# Breakout_DL_IP-M4_rev02.net
KiCad netlist of a schematic drawn in EAGLE
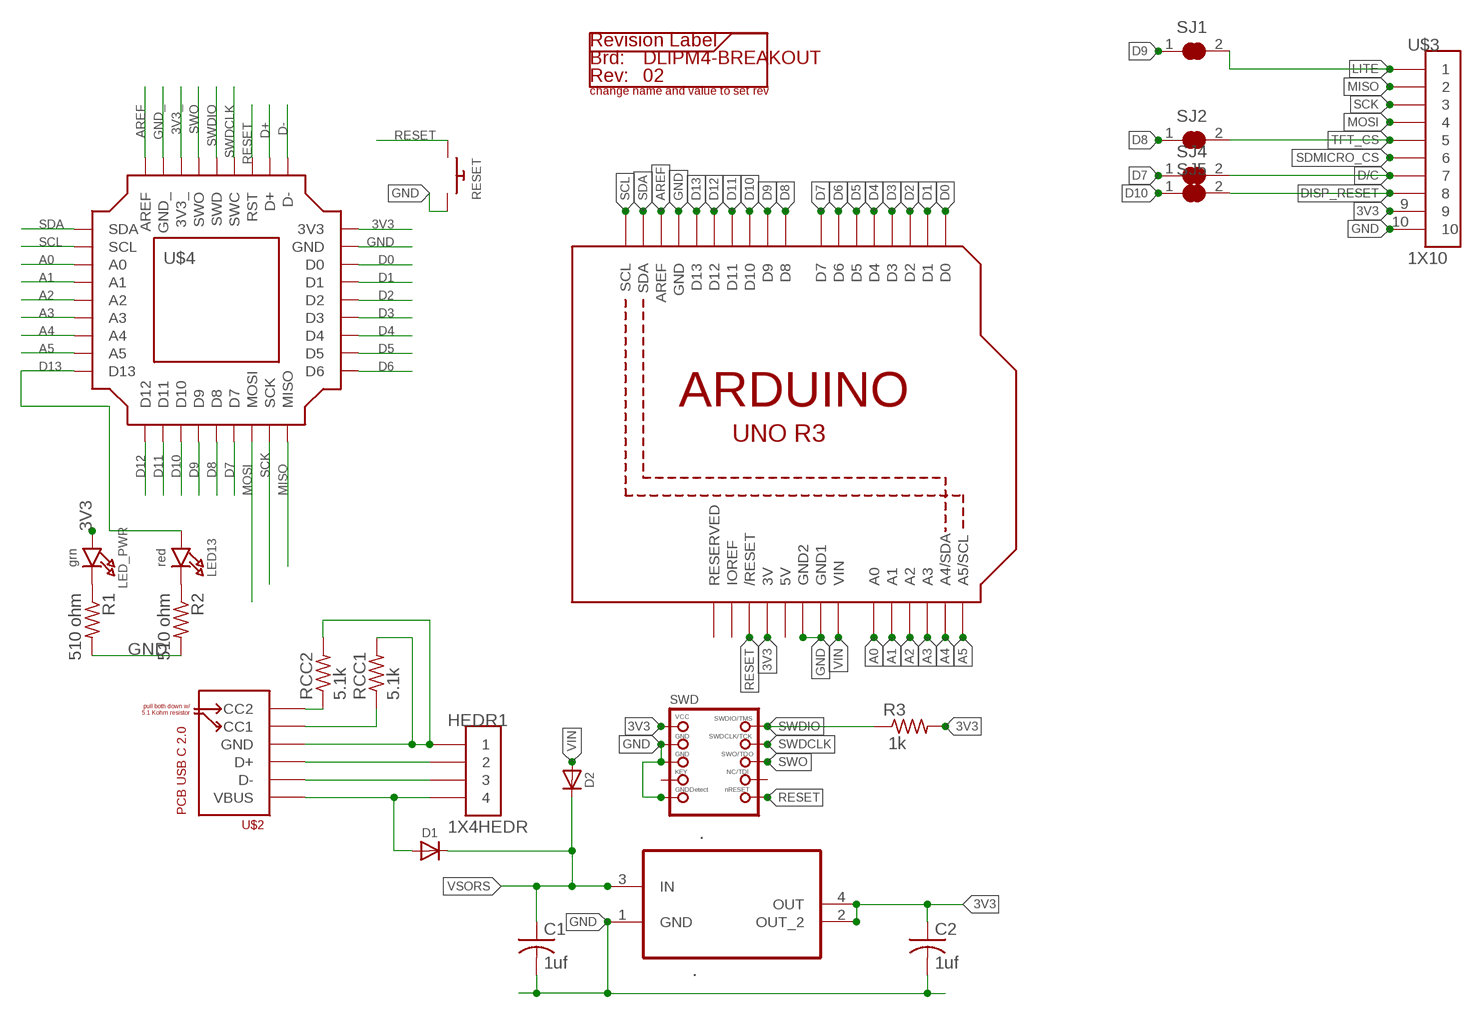
[diagram p0: schematic, sheet 1]

(export (version "E")
  (design (tool "Eeschema 10.0.6"))
  (components
    (comp (ref ".")
      (value ".")
      (footprint "eagle-import:SOT230P700X180-4N")
      (fields (field (name "MF") "Analog Devices") (field (name "MP") "ADP3339AKCZ-3.3-RL"))
      (libsource (lib "eagle-import") (part "VREG-1.5A-3.3V-LRG"))
    )
    (comp (ref "C1")
      (value "1uf")
      (footprint "eagle-import:TG-0603")
      (libsource (lib "eagle-import") (part "C-TG_0603"))
    )
    (comp (ref "C2")
      (value "1uf")
      (footprint "eagle-import:TG-0603")
      (libsource (lib "eagle-import") (part "C-TG_0603"))
    )
    (comp (ref "D1")
      (value "DIODESOD-123")
      (footprint "eagle-import:SOD-123")
      (libsource (lib "eagle-import") (part "DIODESOD-123"))
    )
    (comp (ref "D2")
      (value "DIODESOD-123")
      (footprint "eagle-import:SOD-123")
      (libsource (lib "eagle-import") (part "DIODESOD-123"))
    )
    (comp (ref "DLIPM4-BREAKOUT")
      (value "02")
      (footprint "eagle-import:REVISION_LABEL_LONG")
      (libsource (lib "eagle-import") (part "REVISION_LABELLONG"))
    )
    (comp (ref "HEDR1")
      (value "1X4HEDR")
      (footprint "eagle-import:1X4_HEDR")
      (libsource (lib "eagle-import") (part "1X4HEDR"))
    )
    (comp (ref "LED13")
      (value "red")
      (footprint "eagle-import:MICROBUILDER_CHIPLED_1206_NOOUTLINE")
      (libsource (lib "eagle-import") (part "LED-MICROBUILDER1206_NOOUTLINE"))
    )
    (comp (ref "LED_PWR")
      (value "grn")
      (footprint "eagle-import:MICROBUILDER_CHIPLED_1206_NOOUTLINE")
      (libsource (lib "eagle-import") (part "LED-MICROBUILDER1206_NOOUTLINE"))
    )
    (comp (ref "R1")
      (value "510 ohm")
      (footprint "eagle-import:TG-0603")
      (libsource (lib "eagle-import") (part "R_TG_0603"))
    )
    (comp (ref "R2")
      (value "510 ohm")
      (footprint "eagle-import:TG-0603")
      (libsource (lib "eagle-import") (part "R_TG_0603"))
    )
    (comp (ref "R3")
      (value "1k")
      (footprint "eagle-import:TG-0603")
      (libsource (lib "eagle-import") (part "R_TG_0603"))
    )
    (comp (ref "RCC1")
      (value "5.1k")
      (footprint "eagle-import:TG-0603")
      (libsource (lib "eagle-import") (part "R_TG_0603"))
    )
    (comp (ref "RCC2")
      (value "5.1k")
      (footprint "eagle-import:TG-0603")
      (libsource (lib "eagle-import") (part "R_TG_0603"))
    )
    (comp (ref "RESET")
      (value "SWITCH_PUSHBUTTONEVQ-PE")
      (footprint "eagle-import:TACT_PANA-EVQ")
      (libsource (lib "eagle-import") (part "SWITCH_PUSHBUTTONEVQ-PE"))
    )
    (comp (ref "SJ1")
      (value "JUMPER_CLOSEDTEMP")
      (footprint "eagle-import:SOLDERJUMPER_CLOSEDWIRE")
      (libsource (lib "eagle-import") (part "JUMPER_CLOSEDTEMP"))
    )
    (comp (ref "SJ2")
      (value "JUMPER_CLOSEDTEMP")
      (footprint "eagle-import:SOLDERJUMPER_CLOSEDWIRE")
      (libsource (lib "eagle-import") (part "JUMPER_CLOSEDTEMP"))
    )
    (comp (ref "SJ4")
      (value "JUMPER_CLOSEDTEMP")
      (footprint "eagle-import:SOLDERJUMPER_CLOSEDWIRE")
      (libsource (lib "eagle-import") (part "JUMPER_CLOSEDTEMP"))
    )
    (comp (ref "SJ5")
      (value "JUMPER_CLOSEDTEMP")
      (footprint "eagle-import:SOLDERJUMPER_CLOSEDWIRE")
      (libsource (lib "eagle-import") (part "JUMPER_CLOSEDTEMP"))
    )
    (comp (ref "SWD")
      (value "CON-SWD-JTAG-CORTEXBOXPOSTS")
      (footprint "eagle-import:2X05_1.27MM_BOX_POSTS")
      (libsource (lib "eagle-import") (part "CON-SWD-JTAG-CORTEXBOXPOSTS"))
    )
    (comp (ref "U$2")
      (value "USB-C-PCB-USB-2.0-TYPE-CDS_2")
      (footprint "eagle-import:USB_TYPE_C_DS_2")
      (libsource (lib "eagle-import") (part "USB-C-PCB-USB-2.0-TYPE-CDS_2"))
    )
    (comp (ref "U$3")
      (value "1X10")
      (footprint "eagle-import:1X10_HEDR")
      (libsource (lib "eagle-import") (part "1X10"))
    )
    (comp (ref "U$4")
      (value "DATALORE_IP_M4FOOTPRINT")
      (footprint "eagle-import:DL_IP_36-100MIL-FOOTPRINT")
      (libsource (lib "eagle-import") (part "DATALORE_IP_M4FOOTPRINT"))
    )
    (comp (ref "U1")
      (value "ARDUINOR3-BPLACE")
      (footprint "eagle-import:ARDUINOR3-BPLACE")
      (libsource (lib "eagle-import") (part "ARDUINOR3-BPLACE"))
    )
  )
  (nets
    (net (code "1") (name "/3V3_") (class "Default")
      (node (ref "U$4") (pin "3") (pinfunction "3V3__3") (pintype "bidirectional"))
    )
    (net (code "2") (name "/5V") (class "Default")
      (node (ref "U1") (pin "5V") (pinfunction "5V_5V") (pintype "power_in"))
    )
    (net (code "3") (name "/D+") (class "Default")
      (node (ref "HEDR1") (pin "2") (pinfunction "2_2") (pintype "bidirectional"))
      (node (ref "U$2") (pin "A6") (pinfunction "D+_A6") (pintype "bidirectional"))
      (node (ref "U$2") (pin "B6") (pinfunction "D+_B6") (pintype "bidirectional"))
      (node (ref "U$4") (pin "8") (pinfunction "D+_8") (pintype "bidirectional"))
    )
    (net (code "4") (name "/D-") (class "Default")
      (node (ref "HEDR1") (pin "3") (pinfunction "3_3") (pintype "bidirectional"))
      (node (ref "U$2") (pin "A7") (pinfunction "D-_A7") (pintype "bidirectional"))
      (node (ref "U$2") (pin "B7") (pinfunction "D-_B7") (pintype "bidirectional"))
      (node (ref "U$4") (pin "9") (pinfunction "D-_9") (pintype "bidirectional"))
    )
    (net (code "5") (name "/GND_") (class "Default")
      (node (ref "U$4") (pin "2") (pinfunction "GND__2") (pintype "bidirectional"))
    )
    (net (code "6") (name "3V3") (class "Default")
      (node (ref ".") (pin "2") (pinfunction "OUT_2_2") (pintype "output"))
      (node (ref ".") (pin "4") (pinfunction "OUT_4") (pintype "output"))
      (node (ref "C2") (pin "1") (pinfunction "1_1") (pintype "passive"))
      (node (ref "LED_PWR") (pin "A") (pinfunction "A_A") (pintype "passive"))
      (node (ref "R3") (pin "2") (pinfunction "2_2") (pintype "passive"))
      (node (ref "SWD") (pin "1") (pinfunction "VCC_1") (pintype "power_in"))
      (node (ref "U$3") (pin "9") (pinfunction "9_9") (pintype "bidirectional"))
      (node (ref "U$4") (pin "10") (pinfunction "3V3_10") (pintype "bidirectional"))
      (node (ref "U1") (pin "3V") (pinfunction "3V_3V") (pintype "power_in"))
    )
    (net (code "7") (name "A0") (class "Default")
      (node (ref "U$4") (pin "34") (pinfunction "A0_34") (pintype "bidirectional"))
      (node (ref "U1") (pin "A0") (pinfunction "A0_A0") (pintype "bidirectional"))
    )
    (net (code "8") (name "A1") (class "Default")
      (node (ref "U$4") (pin "33") (pinfunction "A1_33") (pintype "bidirectional"))
      (node (ref "U1") (pin "A1") (pinfunction "A1_A1") (pintype "bidirectional"))
    )
    (net (code "9") (name "A2") (class "Default")
      (node (ref "U$4") (pin "32") (pinfunction "A2_32") (pintype "bidirectional"))
      (node (ref "U1") (pin "A2") (pinfunction "A2_A2") (pintype "bidirectional"))
    )
    (net (code "10") (name "A3") (class "Default")
      (node (ref "U$4") (pin "31") (pinfunction "A3_31") (pintype "bidirectional"))
      (node (ref "U1") (pin "A3") (pinfunction "A3_A3") (pintype "bidirectional"))
    )
    (net (code "11") (name "A4") (class "Default")
      (node (ref "U$4") (pin "30") (pinfunction "A4_30") (pintype "bidirectional"))
      (node (ref "U1") (pin "A4") (pinfunction "A4/SDA_A4") (pintype "bidirectional"))
    )
    (net (code "12") (name "A5") (class "Default")
      (node (ref "U$4") (pin "29") (pinfunction "A5_29") (pintype "bidirectional"))
      (node (ref "U1") (pin "A5") (pinfunction "A5/SCL_A5") (pintype "bidirectional"))
    )
    (net (code "13") (name "AREF") (class "Default")
      (node (ref "U$4") (pin "1") (pinfunction "AREF_1") (pintype "bidirectional"))
      (node (ref "U1") (pin "AREF") (pinfunction "AREF_AREF") (pintype "bidirectional"))
    )
    (net (code "14") (name "D0") (class "Default")
      (node (ref "U$4") (pin "12") (pinfunction "D0_12") (pintype "bidirectional"))
      (node (ref "U1") (pin "D0") (pinfunction "D0_D0") (pintype "bidirectional"))
    )
    (net (code "15") (name "D1") (class "Default")
      (node (ref "U$4") (pin "13") (pinfunction "D1_13") (pintype "bidirectional"))
      (node (ref "U1") (pin "D1") (pinfunction "D1_D1") (pintype "bidirectional"))
    )
    (net (code "16") (name "D2") (class "Default")
      (node (ref "U$4") (pin "14") (pinfunction "D2_14") (pintype "bidirectional"))
      (node (ref "U1") (pin "D2") (pinfunction "D2_D2") (pintype "bidirectional"))
    )
    (net (code "17") (name "D3") (class "Default")
      (node (ref "U$4") (pin "15") (pinfunction "D3_15") (pintype "bidirectional"))
      (node (ref "U1") (pin "D3") (pinfunction "D3_D3") (pintype "bidirectional"))
    )
    (net (code "18") (name "D4") (class "Default")
      (node (ref "U$4") (pin "16") (pinfunction "D4_16") (pintype "bidirectional"))
      (node (ref "U1") (pin "D4") (pinfunction "D4_D4") (pintype "bidirectional"))
    )
    (net (code "19") (name "D5") (class "Default")
      (node (ref "U$4") (pin "17") (pinfunction "D5_17") (pintype "bidirectional"))
      (node (ref "U1") (pin "D5") (pinfunction "D5_D5") (pintype "bidirectional"))
    )
    (net (code "20") (name "D6") (class "Default")
      (node (ref "U$4") (pin "18") (pinfunction "D6_18") (pintype "bidirectional"))
      (node (ref "U1") (pin "D6") (pinfunction "D6_D6") (pintype "bidirectional"))
    )
    (net (code "21") (name "D7") (class "Default")
      (node (ref "SJ4") (pin "1") (pinfunction "1_1") (pintype "passive"))
      (node (ref "U$4") (pin "22") (pinfunction "D7_22") (pintype "bidirectional"))
      (node (ref "U1") (pin "D7") (pinfunction "D7_D7") (pintype "bidirectional"))
    )
    (net (code "22") (name "D8") (class "Default")
      (node (ref "SJ2") (pin "1") (pinfunction "1_1") (pintype "passive"))
      (node (ref "U$4") (pin "23") (pinfunction "D8_23") (pintype "bidirectional"))
      (node (ref "U1") (pin "D8") (pinfunction "D8_D8") (pintype "bidirectional"))
    )
    (net (code "23") (name "D9") (class "Default")
      (node (ref "SJ1") (pin "1") (pinfunction "1_1") (pintype "passive"))
      (node (ref "U$4") (pin "24") (pinfunction "D9_24") (pintype "bidirectional"))
      (node (ref "U1") (pin "D9") (pinfunction "D9_D9") (pintype "bidirectional"))
    )
    (net (code "24") (name "D10") (class "Default")
      (node (ref "SJ5") (pin "1") (pinfunction "1_1") (pintype "passive"))
      (node (ref "U$4") (pin "25") (pinfunction "D10_25") (pintype "bidirectional"))
      (node (ref "U1") (pin "D10") (pinfunction "D10_D10") (pintype "bidirectional"))
    )
    (net (code "25") (name "D11") (class "Default")
      (node (ref "U$4") (pin "26") (pinfunction "D11_26") (pintype "bidirectional"))
      (node (ref "U1") (pin "D11") (pinfunction "D11_D11") (pintype "bidirectional"))
    )
    (net (code "26") (name "D12") (class "Default")
      (node (ref "U$4") (pin "27") (pinfunction "D12_27") (pintype "bidirectional"))
      (node (ref "U1") (pin "D12") (pinfunction "D12_D12") (pintype "bidirectional"))
    )
    (net (code "27") (name "D13") (class "Default")
      (node (ref "LED13") (pin "A") (pinfunction "A_A") (pintype "passive"))
      (node (ref "U$4") (pin "28") (pinfunction "D13_28") (pintype "bidirectional"))
      (node (ref "U1") (pin "D13") (pinfunction "D13_D13") (pintype "bidirectional"))
    )
    (net (code "28") (name "DISP_RESET") (class "Default")
      (node (ref "SJ5") (pin "2") (pinfunction "2_2") (pintype "passive"))
      (node (ref "U$3") (pin "8") (pinfunction "8_8") (pintype "bidirectional"))
    )
    (net (code "29") (name "D{slash}C") (class "Default")
      (node (ref "SJ4") (pin "2") (pinfunction "2_2") (pintype "passive"))
      (node (ref "U$3") (pin "7") (pinfunction "7_7") (pintype "bidirectional"))
    )
    (net (code "30") (name "GND") (class "Default")
      (node (ref ".") (pin "1") (pinfunction "GND_1") (pintype "passive"))
      (node (ref "C1") (pin "2") (pinfunction "2_2") (pintype "passive"))
      (node (ref "C2") (pin "2") (pinfunction "2_2") (pintype "passive"))
      (node (ref "HEDR1") (pin "1") (pinfunction "1_1") (pintype "bidirectional"))
      (node (ref "R1") (pin "2") (pinfunction "2_2") (pintype "passive"))
      (node (ref "R2") (pin "2") (pinfunction "2_2") (pintype "passive"))
      (node (ref "RCC1") (pin "2") (pinfunction "2_2") (pintype "passive"))
      (node (ref "RCC2") (pin "2") (pinfunction "2_2") (pintype "passive"))
      (node (ref "RESET") (pin "P$2") (pinfunction "P$2_P$2") (pintype "passive"))
      (node (ref "SWD") (pin "3") (pinfunction "GND_3") (pintype "power_in"))
      (node (ref "SWD") (pin "5") (pinfunction "GND_5") (pintype "power_in"))
      (node (ref "SWD") (pin "9") (pinfunction "GNDDETECT_9") (pintype "bidirectional"))
      (node (ref "U$2") (pin "A1") (pinfunction "GND_A1") (pintype "bidirectional"))
      (node (ref "U$2") (pin "A12") (pinfunction "GND_A12") (pintype "bidirectional"))
      (node (ref "U$2") (pin "B1") (pinfunction "GND_B1") (pintype "bidirectional"))
      (node (ref "U$2") (pin "B12") (pinfunction "GND_B12") (pintype "bidirectional"))
      (node (ref "U$3") (pin "10") (pinfunction "10_10") (pintype "bidirectional"))
      (node (ref "U$4") (pin "11") (pinfunction "GND_11") (pintype "bidirectional"))
      (node (ref "U1") (pin "GND") (pinfunction "GND_GND") (pintype "power_in"))
      (node (ref "U1") (pin "GND1") (pinfunction "GND1_GND1") (pintype "power_in"))
      (node (ref "U1") (pin "GND2") (pinfunction "GND2_GND2") (pintype "power_in"))
    )
    (net (code "31") (name "LITE") (class "Default")
      (node (ref "SJ1") (pin "2") (pinfunction "2_2") (pintype "passive"))
      (node (ref "U$3") (pin "1") (pinfunction "1_1") (pintype "bidirectional"))
    )
    (net (code "32") (name "MISO") (class "Default")
      (node (ref "U$3") (pin "2") (pinfunction "2_2") (pintype "bidirectional"))
      (node (ref "U$4") (pin "19") (pinfunction "MISO_19") (pintype "bidirectional"))
    )
    (net (code "33") (name "MOSI") (class "Default")
      (node (ref "U$3") (pin "4") (pinfunction "4_4") (pintype "bidirectional"))
      (node (ref "U$4") (pin "21") (pinfunction "MOSI_21") (pintype "bidirectional"))
    )
    (net (code "34") (name "Net-(D1-PadA)") (class "Default")
      (node (ref "D1") (pin "A") (pinfunction "A_A") (pintype "passive"))
      (node (ref "HEDR1") (pin "4") (pinfunction "4_4") (pintype "bidirectional"))
      (node (ref "U$2") (pin "A4") (pinfunction "VBUS_A4") (pintype "bidirectional"))
      (node (ref "U$2") (pin "A9") (pinfunction "VBUS_A9") (pintype "bidirectional"))
      (node (ref "U$2") (pin "B4") (pinfunction "VBUS_B4") (pintype "bidirectional"))
      (node (ref "U$2") (pin "B9") (pinfunction "VBUS_B9") (pintype "bidirectional"))
    )
    (net (code "35") (name "Net-(LED13-PadC)") (class "Default")
      (node (ref "LED13") (pin "C") (pinfunction "C_C") (pintype "passive"))
      (node (ref "R2") (pin "1") (pinfunction "1_1") (pintype "passive"))
    )
    (net (code "36") (name "Net-(LED_PWR-PadC)") (class "Default")
      (node (ref "LED_PWR") (pin "C") (pinfunction "C_C") (pintype "passive"))
      (node (ref "R1") (pin "1") (pinfunction "1_1") (pintype "passive"))
    )
    (net (code "37") (name "Net-(U$2-CC1)") (class "Default")
      (node (ref "RCC1") (pin "1") (pinfunction "1_1") (pintype "passive"))
      (node (ref "U$2") (pin "A5") (pinfunction "CC1_A5") (pintype "bidirectional"))
    )
    (net (code "38") (name "Net-(U$2-CC2)") (class "Default")
      (node (ref "RCC2") (pin "1") (pinfunction "1_1") (pintype "passive"))
      (node (ref "U$2") (pin "B5") (pinfunction "CC2_B5") (pintype "bidirectional"))
    )
    (net (code "39") (name "RESET") (class "Default")
      (node (ref "RESET") (pin "P$1") (pinfunction "P$1_P$1") (pintype "passive"))
      (node (ref "SWD") (pin "10") (pinfunction "NRESET_10") (pintype "bidirectional"))
      (node (ref "U$4") (pin "7") (pinfunction "RST_7") (pintype "bidirectional"))
      (node (ref "U1") (pin "RESET") (pinfunction "/RESET_RESET") (pintype "bidirectional"))
    )
    (net (code "40") (name "SCK") (class "Default")
      (node (ref "U$3") (pin "3") (pinfunction "3_3") (pintype "bidirectional"))
      (node (ref "U$4") (pin "20") (pinfunction "SCK_20") (pintype "bidirectional"))
    )
    (net (code "41") (name "SCL") (class "Default")
      (node (ref "U$4") (pin "35") (pinfunction "SCL_35") (pintype "bidirectional"))
      (node (ref "U1") (pin "SCL") (pinfunction "SCL_SCL") (pintype "bidirectional"))
    )
    (net (code "42") (name "SDA") (class "Default")
      (node (ref "U$4") (pin "36") (pinfunction "SDA_36") (pintype "bidirectional"))
      (node (ref "U1") (pin "SDA") (pinfunction "SDA_SDA") (pintype "bidirectional"))
    )
    (net (code "43") (name "SDMICRO_CS") (class "Default")
      (node (ref "U$3") (pin "6") (pinfunction "6_6") (pintype "bidirectional"))
    )
    (net (code "44") (name "SWDCLK") (class "Default")
      (node (ref "SWD") (pin "4") (pinfunction "SWDCLK_4") (pintype "bidirectional"))
      (node (ref "U$4") (pin "6") (pinfunction "SWC_6") (pintype "bidirectional"))
    )
    (net (code "45") (name "SWDIO") (class "Default")
      (node (ref "R3") (pin "1") (pinfunction "1_1") (pintype "passive"))
      (node (ref "SWD") (pin "2") (pinfunction "SWDIO_2") (pintype "bidirectional"))
      (node (ref "U$4") (pin "5") (pinfunction "SWD_5") (pintype "bidirectional"))
    )
    (net (code "46") (name "SWO") (class "Default")
      (node (ref "SWD") (pin "6") (pinfunction "SWO_6") (pintype "bidirectional"))
      (node (ref "U$4") (pin "4") (pinfunction "SWO_4") (pintype "bidirectional"))
    )
    (net (code "47") (name "TFT_CS") (class "Default")
      (node (ref "SJ2") (pin "2") (pinfunction "2_2") (pintype "passive"))
      (node (ref "U$3") (pin "5") (pinfunction "5_5") (pintype "bidirectional"))
    )
    (net (code "48") (name "VIN") (class "Default")
      (node (ref "D2") (pin "A") (pinfunction "A_A") (pintype "passive"))
      (node (ref "U1") (pin "VIN") (pinfunction "VIN_VIN") (pintype "power_in"))
    )
    (net (code "49") (name "VSORS") (class "Default")
      (node (ref ".") (pin "3") (pinfunction "IN_3") (pintype "input"))
      (node (ref "C1") (pin "1") (pinfunction "1_1") (pintype "passive"))
      (node (ref "D1") (pin "C") (pinfunction "C_C") (pintype "passive"))
      (node (ref "D2") (pin "C") (pinfunction "C_C") (pintype "passive"))
    )
    (net (code "50") (name "unconnected-(SWD-KEY-Pad7)") (class "Default")
      (node (ref "SWD") (pin "7") (pinfunction "KEY_7") (pintype "bidirectional"))
    )
    (net (code "51") (name "unconnected-(SWD-TDI-Pad8)") (class "Default")
      (node (ref "SWD") (pin "8") (pinfunction "TDI_8") (pintype "bidirectional"))
    )
    (net (code "52") (name "unconnected-(U1-PadIOREF)") (class "Default")
      (node (ref "U1") (pin "IOREF") (pinfunction "IOREF_IOREF") (pintype "output"))
    )
    (net (code "53") (name "unconnected-(U1-PadRESERVED)") (class "Default")
      (node (ref "U1") (pin "RESERVED") (pinfunction "RESERVED_RESERVED") (pintype "no_connect"))
    )
  )
)
